# ButtonsBuzzerLeds.net
KiCad netlist of a schematic drawn in Altium Designer
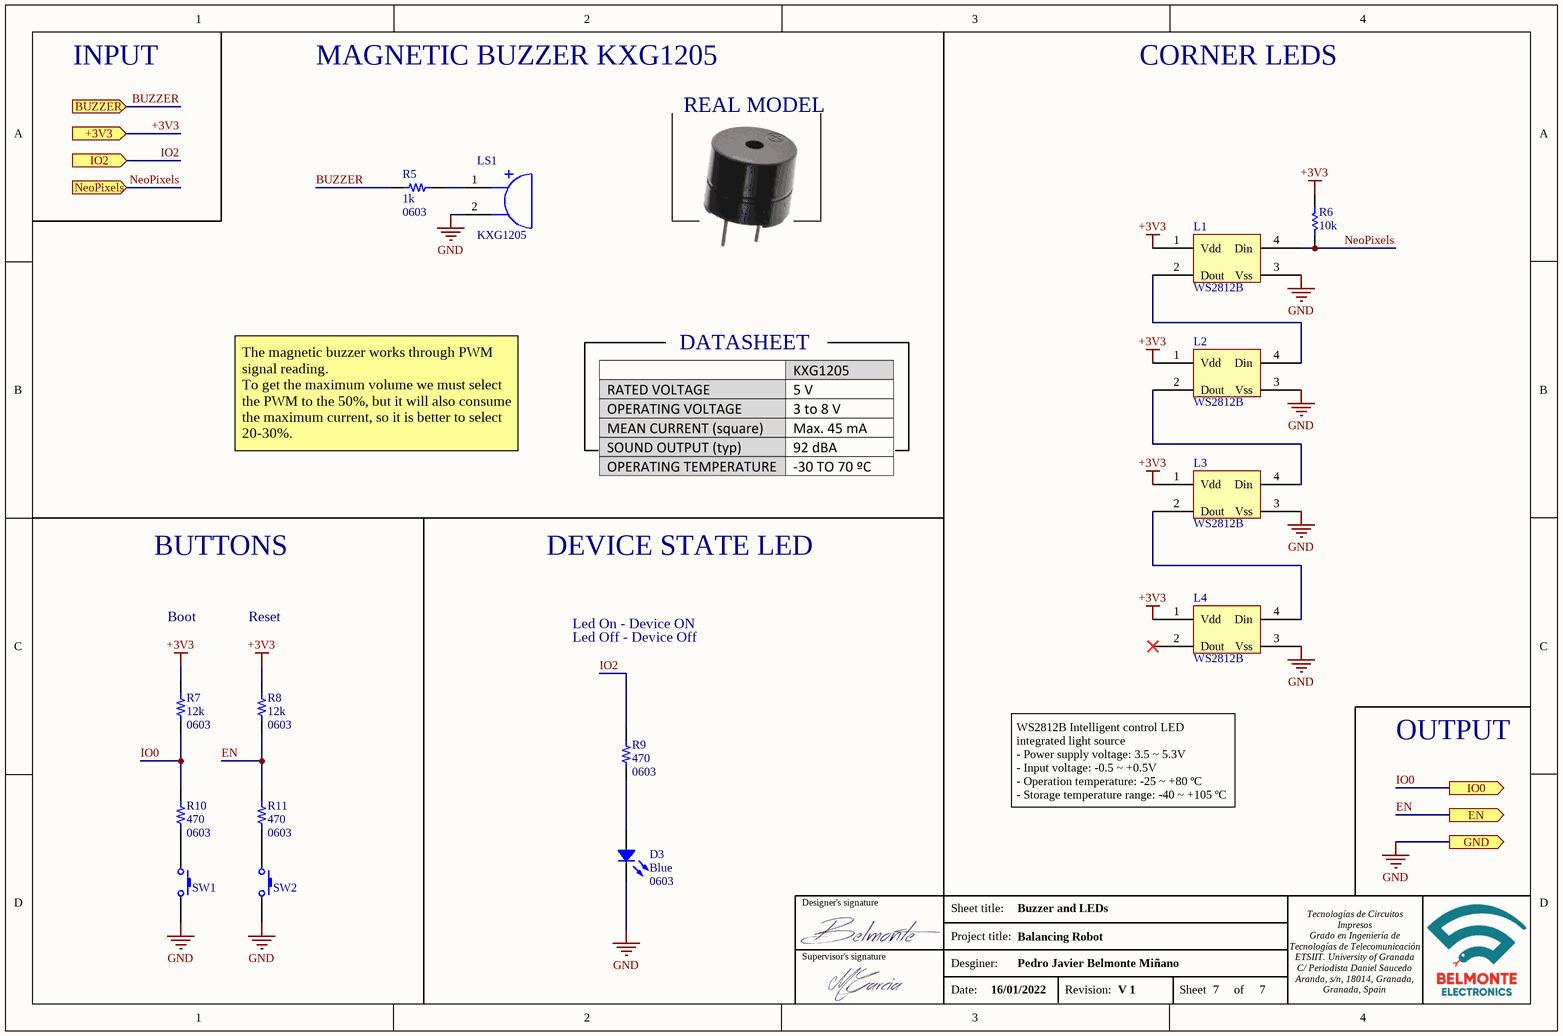
[diagram p0: ButtonsBuzzerLeds.SchDoc]

(export (version "E")
  (design (tool "Eeschema 10.0.6"))
  (components
    (comp (ref "D3")
      (value "Blue")
      (footprint "LED 0603_1608 BLUE")
      (description "LED BLUE 0603 SMD")
      (fields
        (field (name "PART NUMBER") "VLMB1300-GS08")
        (field (name "MANUFACTURER") "Vishay Semiconductor Opto Division")
        (field (name "SIZE") "0603")
      )
      (libsource (lib "ControlBoard") (part "LED"))
    )
    (comp (ref "L1")
      (value "WS2812B")
      (footprint "WS2812B")
      (description "Intelligentcontrol LED integrated light source WS2812B")
      (libsource (lib "ControlBoard") (part "WS2812B"))
    )
    (comp (ref "L2")
      (value "WS2812B")
      (footprint "WS2812B")
      (description "Intelligentcontrol LED integrated light source WS2812B")
      (libsource (lib "ControlBoard") (part "WS2812B"))
    )
    (comp (ref "L3")
      (value "WS2812B")
      (footprint "WS2812B")
      (description "Intelligentcontrol LED integrated light source WS2812B")
      (libsource (lib "ControlBoard") (part "WS2812B"))
    )
    (comp (ref "L4")
      (value "WS2812B")
      (footprint "WS2812B")
      (description "Intelligentcontrol LED integrated light source WS2812B")
      (libsource (lib "ControlBoard") (part "WS2812B"))
    )
    (comp (ref "LS1")
      (value "KXG1205")
      (footprint "BUZZER")
      (description "BUZZER KXG1205")
      (libsource (lib "ControlBoard") (part "Buzzer"))
    )
    (comp (ref "R5")
      (value "1k")
      (footprint "RES 0603_1608")
      (description "RES SMD 1K OHM 1% 1/4W 0603")
      (fields
        (field (name "PART NUMBER") "CRCW06031K00FKEAHP")
        (field (name "MANUFACTURER") "Vishay Dale")
        (field (name "SIZE") "0603")
      )
      (libsource (lib "ControlBoard") (part "CRCW06031K00FKEAHP"))
    )
    (comp (ref "R6")
      (value "10k")
      (footprint "0805")
      (description "Resistor")
      (libsource (lib "HeimdalLimiter") (part "Resistor"))
    )
    (comp (ref "R7")
      (value "12k")
      (footprint "RES 0603_1608")
      (description "RES 12K OHM 5% 1/10W 0603")
      (fields
        (field (name "PART NUMBER") "RMCF0603JT12K0")
        (field (name "MANUFACTURER") "Stackpole Electronics Inc")
        (field (name "SIZE") "0603")
      )
      (libsource (lib "ControlBoard") (part "RMCF0603JT12K0"))
    )
    (comp (ref "R8")
      (value "12k")
      (footprint "RES 0603_1608")
      (description "RES 12K OHM 5% 1/10W 0603")
      (fields
        (field (name "PART NUMBER") "RMCF0603JT12K0")
        (field (name "MANUFACTURER") "Stackpole Electronics Inc")
        (field (name "SIZE") "0603")
      )
      (libsource (lib "ControlBoard") (part "RMCF0603JT12K0"))
    )
    (comp (ref "R9")
      (value "470")
      (footprint "RES 0603_1608")
      (description "RES 470 OHM 5% 1/10W 0603")
      (fields
        (field (name "PART NUMBER") "RMCF0603JT470R")
        (field (name "MANUFACTURER") "Stackpole Electronics Inc")
        (field (name "SIZE") "0603")
      )
      (libsource (lib "ControlBoard") (part "RMCF0603JT470R"))
    )
    (comp (ref "R10")
      (value "470")
      (footprint "RES 0603_1608")
      (description "RES 470 OHM 5% 1/10W 0603")
      (fields
        (field (name "PART NUMBER") "RMCF0603JT470R")
        (field (name "MANUFACTURER") "Stackpole Electronics Inc")
        (field (name "SIZE") "0603")
      )
      (libsource (lib "ControlBoard") (part "RMCF0603JT470R"))
    )
    (comp (ref "R11")
      (value "470")
      (footprint "RES 0603_1608")
      (description "RES 470 OHM 5% 1/10W 0603")
      (fields
        (field (name "PART NUMBER") "RMCF0603JT470R")
        (field (name "MANUFACTURER") "Stackpole Electronics Inc")
        (field (name "SIZE") "0603")
      )
      (libsource (lib "ControlBoard") (part "RMCF0603JT470R"))
    )
    (comp (ref "SW1")
      (value "FSMSMTR")
      (footprint "TECO-FSMSMTR_V")
      (description "FSMSM Push Button Switch, 50 mA, -35 to 85 degC, 2-Pin SMD, RoHS, Tape and Reel")
      (fields (field (name "MANUFACTURER") "TE Connectivity"))
      (libsource (lib "TopBoardLib") (part "CMP-2000-07501-1"))
    )
    (comp (ref "SW2")
      (value "FSMSMTR")
      (footprint "TECO-FSMSMTR_V")
      (description "FSMSM Push Button Switch, 50 mA, -35 to 85 degC, 2-Pin SMD, RoHS, Tape and Reel")
      (fields (field (name "MANUFACTURER") "TE Connectivity"))
      (libsource (lib "TopBoardLib") (part "CMP-2000-07501-1"))
    )
  )
  (nets
    (net (code "1") (name "+3V3") (class "Default")
      (node (ref "L1") (pin "1") (pinfunction "Vdd_1") (pintype "passive"))
      (node (ref "L2") (pin "1") (pinfunction "Vdd_1") (pintype "passive"))
      (node (ref "L3") (pin "1") (pinfunction "Vdd_1") (pintype "passive"))
      (node (ref "L4") (pin "1") (pinfunction "Vdd_1") (pintype "passive"))
      (node (ref "R6") (pin "1") (pinfunction "1_1") (pintype "passive"))
      (node (ref "R7") (pin "1") (pinfunction "1_1") (pintype "passive"))
      (node (ref "R8") (pin "1") (pinfunction "1_1") (pintype "passive"))
    )
    (net (code "2") (name "/BUZZER") (class "Default")
      (node (ref "R5") (pin "2") (pinfunction "2_2") (pintype "passive"))
    )
    (net (code "3") (name "/EN") (class "Default")
      (node (ref "R11") (pin "1") (pinfunction "1_1") (pintype "passive"))
      (node (ref "R8") (pin "2") (pinfunction "2_2") (pintype "passive"))
    )
    (net (code "4") (name "/IO0") (class "Default")
      (node (ref "R10") (pin "1") (pinfunction "1_1") (pintype "passive"))
      (node (ref "R7") (pin "2") (pinfunction "2_2") (pintype "passive"))
    )
    (net (code "5") (name "/IO2") (class "Default")
      (node (ref "R9") (pin "1") (pinfunction "1_1") (pintype "passive"))
    )
    (net (code "6") (name "/NeoPixels") (class "Default")
      (node (ref "L1") (pin "4") (pinfunction "Din_4") (pintype "passive"))
      (node (ref "R6") (pin "2") (pinfunction "2_2") (pintype "passive"))
    )
    (net (code "7") (name "GND") (class "Default")
      (node (ref "D3") (pin "2") (pinfunction "2_2") (pintype "passive"))
      (node (ref "L1") (pin "3") (pinfunction "Vss_3") (pintype "passive"))
      (node (ref "L2") (pin "3") (pinfunction "Vss_3") (pintype "passive"))
      (node (ref "L3") (pin "3") (pinfunction "Vss_3") (pintype "passive"))
      (node (ref "L4") (pin "3") (pinfunction "Vss_3") (pintype "passive"))
      (node (ref "LS1") (pin "2") (pinfunction "-_2") (pintype "passive"))
      (node (ref "SW1") (pin "2") (pinfunction "2_2") (pintype "passive"))
      (node (ref "SW2") (pin "2") (pinfunction "2_2") (pintype "passive"))
    )
    (net (code "8") (name "Net-(D3-Pad1)") (class "Default")
      (node (ref "D3") (pin "1") (pinfunction "1_1") (pintype "passive"))
      (node (ref "R9") (pin "2") (pinfunction "2_2") (pintype "passive"))
    )
    (net (code "9") (name "Net-(L1-Dout)") (class "Default")
      (node (ref "L1") (pin "2") (pinfunction "Dout_2") (pintype "passive"))
      (node (ref "L2") (pin "4") (pinfunction "Din_4") (pintype "passive"))
    )
    (net (code "10") (name "Net-(L2-Dout)") (class "Default")
      (node (ref "L2") (pin "2") (pinfunction "Dout_2") (pintype "passive"))
      (node (ref "L3") (pin "4") (pinfunction "Din_4") (pintype "passive"))
    )
    (net (code "11") (name "Net-(L3-Dout)") (class "Default")
      (node (ref "L3") (pin "2") (pinfunction "Dout_2") (pintype "passive"))
      (node (ref "L4") (pin "4") (pinfunction "Din_4") (pintype "passive"))
    )
    (net (code "12") (name "Net-(LS1-+)") (class "Default")
      (node (ref "LS1") (pin "1") (pinfunction "+_1") (pintype "passive"))
      (node (ref "R5") (pin "1") (pinfunction "1_1") (pintype "passive"))
    )
    (net (code "13") (name "Net-(R10-Pad2)") (class "Default")
      (node (ref "R10") (pin "2") (pinfunction "2_2") (pintype "passive"))
      (node (ref "SW1") (pin "1") (pinfunction "1_1") (pintype "passive"))
    )
    (net (code "14") (name "Net-(R11-Pad2)") (class "Default")
      (node (ref "R11") (pin "2") (pinfunction "2_2") (pintype "passive"))
      (node (ref "SW2") (pin "1") (pinfunction "1_1") (pintype "passive"))
    )
    (net (code "15") (name "unconnected-(L4-Dout-Pad2)") (class "Default")
      (node (ref "L4") (pin "2") (pinfunction "Dout_2") (pintype "passive+no_connect"))
    )
  )
)
